# 20200123_second_Platine_Power.net
KiCad netlist of a schematic drawn in EAGLE
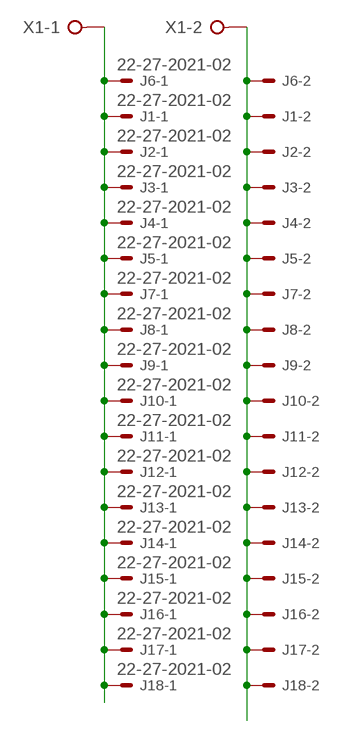
[diagram p0: schematic, sheet 1]

(export (version "E")
  (design (tool "Eeschema 10.0.6"))
  (components
    (comp (ref "J1")
      (value "22-27-2021-02")
      (footprint "eagle-import:6410-02")
      (libsource (lib "eagle-import") (part "22-?-0227-2021"))
    )
    (comp (ref "J2")
      (value "22-27-2021-02")
      (footprint "eagle-import:6410-02")
      (libsource (lib "eagle-import") (part "22-?-0227-2021"))
    )
    (comp (ref "J3")
      (value "22-27-2021-02")
      (footprint "eagle-import:6410-02")
      (libsource (lib "eagle-import") (part "22-?-0227-2021"))
    )
    (comp (ref "J4")
      (value "22-27-2021-02")
      (footprint "eagle-import:6410-02")
      (libsource (lib "eagle-import") (part "22-?-0227-2021"))
    )
    (comp (ref "J5")
      (value "22-27-2021-02")
      (footprint "eagle-import:6410-02")
      (libsource (lib "eagle-import") (part "22-?-0227-2021"))
    )
    (comp (ref "J6")
      (value "22-27-2021-02")
      (footprint "eagle-import:6410-02")
      (libsource (lib "eagle-import") (part "22-?-0227-2021"))
    )
    (comp (ref "J7")
      (value "22-27-2021-02")
      (footprint "eagle-import:6410-02")
      (libsource (lib "eagle-import") (part "22-?-0227-2021"))
    )
    (comp (ref "J8")
      (value "22-27-2021-02")
      (footprint "eagle-import:6410-02")
      (libsource (lib "eagle-import") (part "22-?-0227-2021"))
    )
    (comp (ref "J9")
      (value "22-27-2021-02")
      (footprint "eagle-import:6410-02")
      (libsource (lib "eagle-import") (part "22-?-0227-2021"))
    )
    (comp (ref "J10")
      (value "22-27-2021-02")
      (footprint "eagle-import:6410-02")
      (libsource (lib "eagle-import") (part "22-?-0227-2021"))
    )
    (comp (ref "J11")
      (value "22-27-2021-02")
      (footprint "eagle-import:6410-02")
      (libsource (lib "eagle-import") (part "22-?-0227-2021"))
    )
    (comp (ref "J12")
      (value "22-27-2021-02")
      (footprint "eagle-import:6410-02")
      (libsource (lib "eagle-import") (part "22-?-0227-2021"))
    )
    (comp (ref "J13")
      (value "22-27-2021-02")
      (footprint "eagle-import:6410-02")
      (libsource (lib "eagle-import") (part "22-?-0227-2021"))
    )
    (comp (ref "J14")
      (value "22-27-2021-02")
      (footprint "eagle-import:6410-02")
      (libsource (lib "eagle-import") (part "22-?-0227-2021"))
    )
    (comp (ref "J15")
      (value "22-27-2021-02")
      (footprint "eagle-import:6410-02")
      (libsource (lib "eagle-import") (part "22-?-0227-2021"))
    )
    (comp (ref "J16")
      (value "22-27-2021-02")
      (footprint "eagle-import:6410-02")
      (libsource (lib "eagle-import") (part "22-?-0227-2021"))
    )
    (comp (ref "J17")
      (value "22-27-2021-02")
      (footprint "eagle-import:6410-02")
      (libsource (lib "eagle-import") (part "22-?-0227-2021"))
    )
    (comp (ref "J18")
      (value "22-27-2021-02")
      (footprint "eagle-import:6410-02")
      (libsource (lib "eagle-import") (part "22-?-0227-2021"))
    )
    (comp (ref "X1")
      (value "W237-02P")
      (footprint "eagle-import:W237-132")
      (libsource (lib "eagle-import") (part "W237-02P"))
    )
  )
  (nets
    (net (code "1") (name "Net-(J10A-S)") (class "Default")
      (node (ref "J1") (pin "1") (pinfunction "S_1") (pintype "passive"))
      (node (ref "J10") (pin "1") (pinfunction "S_1") (pintype "passive"))
      (node (ref "J11") (pin "1") (pinfunction "S_1") (pintype "passive"))
      (node (ref "J12") (pin "1") (pinfunction "S_1") (pintype "passive"))
      (node (ref "J13") (pin "1") (pinfunction "S_1") (pintype "passive"))
      (node (ref "J14") (pin "1") (pinfunction "S_1") (pintype "passive"))
      (node (ref "J15") (pin "1") (pinfunction "S_1") (pintype "passive"))
      (node (ref "J16") (pin "1") (pinfunction "S_1") (pintype "passive"))
      (node (ref "J17") (pin "1") (pinfunction "S_1") (pintype "passive"))
      (node (ref "J18") (pin "1") (pinfunction "S_1") (pintype "passive"))
      (node (ref "J2") (pin "1") (pinfunction "S_1") (pintype "passive"))
      (node (ref "J3") (pin "1") (pinfunction "S_1") (pintype "passive"))
      (node (ref "J4") (pin "1") (pinfunction "S_1") (pintype "passive"))
      (node (ref "J5") (pin "1") (pinfunction "S_1") (pintype "passive"))
      (node (ref "J6") (pin "1") (pinfunction "S_1") (pintype "passive"))
      (node (ref "J7") (pin "1") (pinfunction "S_1") (pintype "passive"))
      (node (ref "J8") (pin "1") (pinfunction "S_1") (pintype "passive"))
      (node (ref "J9") (pin "1") (pinfunction "S_1") (pintype "passive"))
      (node (ref "X1") (pin "1") (pinfunction "KL_1") (pintype "passive"))
    )
    (net (code "2") (name "Net-(J10B-S)") (class "Default")
      (node (ref "J1") (pin "2") (pinfunction "S_2") (pintype "passive"))
      (node (ref "J10") (pin "2") (pinfunction "S_2") (pintype "passive"))
      (node (ref "J11") (pin "2") (pinfunction "S_2") (pintype "passive"))
      (node (ref "J12") (pin "2") (pinfunction "S_2") (pintype "passive"))
      (node (ref "J13") (pin "2") (pinfunction "S_2") (pintype "passive"))
      (node (ref "J14") (pin "2") (pinfunction "S_2") (pintype "passive"))
      (node (ref "J15") (pin "2") (pinfunction "S_2") (pintype "passive"))
      (node (ref "J16") (pin "2") (pinfunction "S_2") (pintype "passive"))
      (node (ref "J17") (pin "2") (pinfunction "S_2") (pintype "passive"))
      (node (ref "J18") (pin "2") (pinfunction "S_2") (pintype "passive"))
      (node (ref "J2") (pin "2") (pinfunction "S_2") (pintype "passive"))
      (node (ref "J3") (pin "2") (pinfunction "S_2") (pintype "passive"))
      (node (ref "J4") (pin "2") (pinfunction "S_2") (pintype "passive"))
      (node (ref "J5") (pin "2") (pinfunction "S_2") (pintype "passive"))
      (node (ref "J6") (pin "2") (pinfunction "S_2") (pintype "passive"))
      (node (ref "J7") (pin "2") (pinfunction "S_2") (pintype "passive"))
      (node (ref "J8") (pin "2") (pinfunction "S_2") (pintype "passive"))
      (node (ref "J9") (pin "2") (pinfunction "S_2") (pintype "passive"))
      (node (ref "X1") (pin "2") (pinfunction "KL_2") (pintype "passive"))
    )
  )
)
